# schematic.net
KiCad netlist of a schematic drawn in Altium Designer
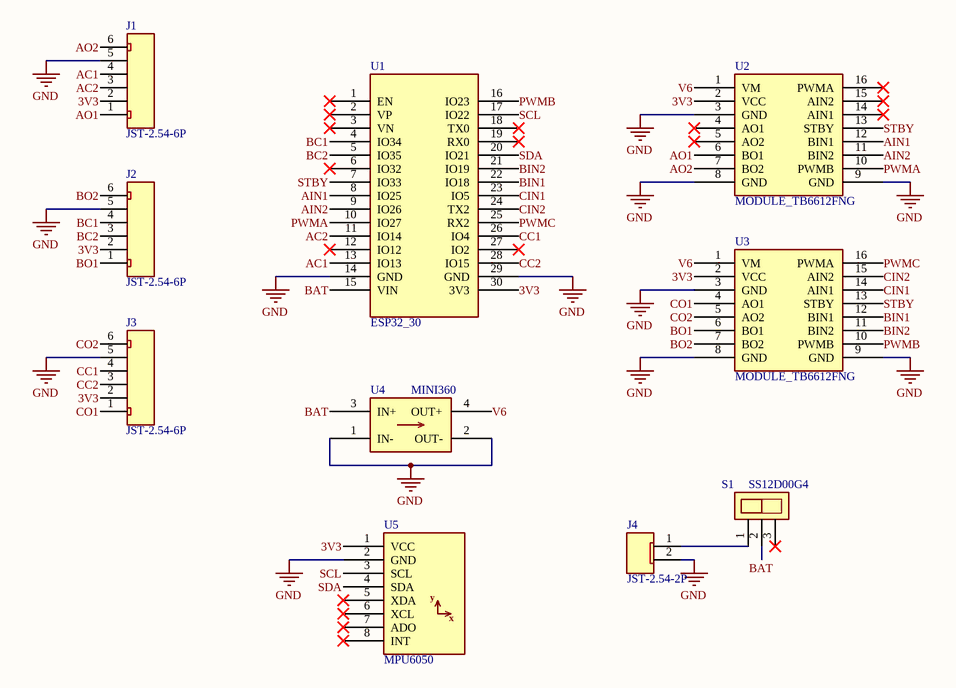
[diagram p0: schematic.SchDoc]

(export (version "E")
  (design (tool "Eeschema 10.0.6"))
  (components
    (comp (ref "J1")
      (value "JST-2.54-6P")
      (footprint "JST-2.54-6P")
      (description "Female Connector JST 6 Vias, 2.54mm.")
      (libsource (lib "Connectors") (part "JST-2.54-6P"))
    )
    (comp (ref "J2")
      (value "JST-2.54-6P")
      (footprint "JST-2.54-6P")
      (description "Female Connector JST 6 Vias, 2.54mm.")
      (libsource (lib "Connectors") (part "JST-2.54-6P"))
    )
    (comp (ref "J3")
      (value "JST-2.54-6P")
      (footprint "JST-2.54-6P")
      (description "Female Connector JST 6 Vias, 2.54mm.")
      (libsource (lib "Connectors") (part "JST-2.54-6P"))
    )
    (comp (ref "J4")
      (value "JST-2.54-2P")
      (footprint "JST-2.54-2P")
      (description "Female Connector JST 2 Vias, 2.54mm.")
      (libsource (lib "Connectors") (part "JST-2.54-2P"))
    )
    (comp (ref "S1")
      (value "SS12D00G4")
      (footprint "SS12D00G4")
      (description "Vertical Slide Switch 3 Pins.")
      (libsource (lib "Buttons & Switches") (part "SS12D00G4"))
    )
    (comp (ref "U1")
      (value "ESP32_30")
      (footprint "ESP32_30")
      (description "Microcontoller Board 30 Pins Wifi 2.4GHz BLE 4.2 ESP32-WROOM-32D")
      (libsource (lib "Espressif Microcontrollers") (part "ESP32_30"))
    )
    (comp (ref "U2")
      (value "MODULE_TB6612FNG")
      (footprint "MODULE_TB6612FNG")
      (description "Module Dual Motor Driver 2.5-13.5V 3.2A Peak 21x18mm")
      (libsource (lib "Motor Drivers") (part "MODULE_TB6612FNG"))
    )
    (comp (ref "U3")
      (value "MODULE_TB6612FNG")
      (footprint "MODULE_TB6612FNG")
      (description "Module Dual Motor Driver 2.5-13.5V 3.2A Peak 21x18mm")
      (libsource (lib "Motor Drivers") (part "MODULE_TB6612FNG"))
    )
    (comp (ref "U4")
      (value "MINI360")
      (footprint "MINI360")
      (description "MODULE BUCK STEP DOWN 3A 18x12mm")
      (libsource (lib "Voltage Regulators") (part "MINI360"))
    )
    (comp (ref "U5")
      (value "MPU6050")
      (footprint "MPU6050")
      (description "IMU ACCEL/GYRO 3-AXIS I2C")
      (libsource (lib "Sensors") (part "MPU6050"))
    )
  )
  (nets
    (net (code "1") (name "/3V3") (class "Default")
      (node (ref "J1") (pin "2") (pintype "passive"))
      (node (ref "J2") (pin "2") (pintype "passive"))
      (node (ref "J3") (pin "2") (pintype "passive"))
      (node (ref "U1") (pin "30") (pinfunction "3V3_30") (pintype "passive"))
      (node (ref "U2") (pin "2") (pinfunction "VCC_2") (pintype "passive"))
      (node (ref "U3") (pin "2") (pinfunction "VCC_2") (pintype "passive"))
      (node (ref "U5") (pin "1") (pinfunction "VCC_1") (pintype "passive"))
    )
    (net (code "2") (name "/AC1") (class "Default")
      (node (ref "J1") (pin "4") (pintype "passive"))
      (node (ref "U1") (pin "13") (pinfunction "IO13_13") (pintype "passive"))
    )
    (net (code "3") (name "/AC2") (class "Default")
      (node (ref "J1") (pin "3") (pintype "passive"))
      (node (ref "U1") (pin "11") (pinfunction "IO14_11") (pintype "passive"))
    )
    (net (code "4") (name "/AIN1") (class "Default")
      (node (ref "U1") (pin "8") (pinfunction "IO25_8") (pintype "passive"))
      (node (ref "U2") (pin "12") (pinfunction "BIN1_12") (pintype "passive"))
    )
    (net (code "5") (name "/AIN2") (class "Default")
      (node (ref "U1") (pin "9") (pinfunction "IO26_9") (pintype "passive"))
      (node (ref "U2") (pin "11") (pinfunction "BIN2_11") (pintype "passive"))
    )
    (net (code "6") (name "/AO1") (class "Default")
      (node (ref "J1") (pin "1") (pintype "passive"))
      (node (ref "U2") (pin "6") (pinfunction "BO1_6") (pintype "passive"))
    )
    (net (code "7") (name "/AO2") (class "Default")
      (node (ref "J1") (pin "6") (pintype "passive"))
      (node (ref "U2") (pin "7") (pinfunction "BO2_7") (pintype "passive"))
    )
    (net (code "8") (name "/BAT") (class "Default")
      (node (ref "S1") (pin "2") (pintype "passive"))
      (node (ref "U1") (pin "15") (pinfunction "VIN_15") (pintype "passive"))
      (node (ref "U4") (pin "3") (pinfunction "IN+_3") (pintype "passive"))
    )
    (net (code "9") (name "/BC1") (class "Default")
      (node (ref "J2") (pin "4") (pintype "passive"))
      (node (ref "U1") (pin "4") (pinfunction "IO34_4") (pintype "passive"))
    )
    (net (code "10") (name "/BC2") (class "Default")
      (node (ref "J2") (pin "3") (pintype "passive"))
      (node (ref "U1") (pin "5") (pinfunction "IO35_5") (pintype "passive"))
    )
    (net (code "11") (name "/BIN1") (class "Default")
      (node (ref "U1") (pin "22") (pinfunction "IO18_22") (pintype "passive"))
      (node (ref "U3") (pin "12") (pinfunction "BIN1_12") (pintype "passive"))
    )
    (net (code "12") (name "/BIN2") (class "Default")
      (node (ref "U1") (pin "21") (pinfunction "IO19_21") (pintype "passive"))
      (node (ref "U3") (pin "11") (pinfunction "BIN2_11") (pintype "passive"))
    )
    (net (code "13") (name "/BO1") (class "Default")
      (node (ref "J2") (pin "1") (pintype "passive"))
      (node (ref "U3") (pin "6") (pinfunction "BO1_6") (pintype "passive"))
    )
    (net (code "14") (name "/BO2") (class "Default")
      (node (ref "J2") (pin "6") (pintype "passive"))
      (node (ref "U3") (pin "7") (pinfunction "BO2_7") (pintype "passive"))
    )
    (net (code "15") (name "/CC1") (class "Default")
      (node (ref "J3") (pin "4") (pintype "passive"))
      (node (ref "U1") (pin "26") (pinfunction "IO4_26") (pintype "passive"))
    )
    (net (code "16") (name "/CC2") (class "Default")
      (node (ref "J3") (pin "3") (pintype "passive"))
      (node (ref "U1") (pin "28") (pinfunction "IO15_28") (pintype "passive"))
    )
    (net (code "17") (name "/CIN1") (class "Default")
      (node (ref "U1") (pin "23") (pinfunction "IO5_23") (pintype "passive"))
      (node (ref "U3") (pin "14") (pinfunction "AIN1_14") (pintype "passive"))
    )
    (net (code "18") (name "/CIN2") (class "Default")
      (node (ref "U1") (pin "24") (pinfunction "TX2_24") (pintype "passive"))
      (node (ref "U3") (pin "15") (pinfunction "AIN2_15") (pintype "passive"))
    )
    (net (code "19") (name "/CO1") (class "Default")
      (node (ref "J3") (pin "1") (pintype "passive"))
      (node (ref "U3") (pin "4") (pinfunction "AO1_4") (pintype "passive"))
    )
    (net (code "20") (name "/CO2") (class "Default")
      (node (ref "J3") (pin "6") (pintype "passive"))
      (node (ref "U3") (pin "5") (pinfunction "AO2_5") (pintype "passive"))
    )
    (net (code "21") (name "/PWMA") (class "Default")
      (node (ref "U1") (pin "10") (pinfunction "IO27_10") (pintype "passive"))
      (node (ref "U2") (pin "10") (pinfunction "PWMB_10") (pintype "passive"))
    )
    (net (code "22") (name "/PWMB") (class "Default")
      (node (ref "U1") (pin "16") (pinfunction "IO23_16") (pintype "passive"))
      (node (ref "U3") (pin "10") (pinfunction "PWMB_10") (pintype "passive"))
    )
    (net (code "23") (name "/PWMC") (class "Default")
      (node (ref "U1") (pin "25") (pinfunction "RX2_25") (pintype "passive"))
      (node (ref "U3") (pin "16") (pinfunction "PWMA_16") (pintype "passive"))
    )
    (net (code "24") (name "/SCL") (class "Default")
      (node (ref "U1") (pin "17") (pinfunction "IO22_17") (pintype "passive"))
      (node (ref "U5") (pin "3") (pinfunction "SCL_3") (pintype "passive"))
    )
    (net (code "25") (name "/SDA") (class "Default")
      (node (ref "U1") (pin "20") (pinfunction "IO21_20") (pintype "passive"))
      (node (ref "U5") (pin "4") (pinfunction "SDA_4") (pintype "passive"))
    )
    (net (code "26") (name "/STBY") (class "Default")
      (node (ref "U1") (pin "7") (pinfunction "IO33_7") (pintype "passive"))
      (node (ref "U2") (pin "13") (pinfunction "STBY_13") (pintype "passive"))
      (node (ref "U3") (pin "13") (pinfunction "STBY_13") (pintype "passive"))
    )
    (net (code "27") (name "/V6") (class "Default")
      (node (ref "U2") (pin "1") (pinfunction "VM_1") (pintype "passive"))
      (node (ref "U3") (pin "1") (pinfunction "VM_1") (pintype "passive"))
      (node (ref "U4") (pin "4") (pinfunction "OUT+_4") (pintype "passive"))
    )
    (net (code "28") (name "GND") (class "Default")
      (node (ref "J1") (pin "5") (pintype "passive"))
      (node (ref "J2") (pin "5") (pintype "passive"))
      (node (ref "J3") (pin "5") (pintype "passive"))
      (node (ref "J4") (pin "2") (pintype "passive"))
      (node (ref "U1") (pin "14") (pinfunction "GND_14") (pintype "passive"))
      (node (ref "U1") (pin "29") (pinfunction "GND_29") (pintype "passive"))
      (node (ref "U2") (pin "3") (pinfunction "GND_3") (pintype "passive"))
      (node (ref "U2") (pin "8") (pinfunction "GND_8") (pintype "passive"))
      (node (ref "U2") (pin "9") (pinfunction "GND_9") (pintype "passive"))
      (node (ref "U3") (pin "3") (pinfunction "GND_3") (pintype "passive"))
      (node (ref "U3") (pin "8") (pinfunction "GND_8") (pintype "passive"))
      (node (ref "U3") (pin "9") (pinfunction "GND_9") (pintype "passive"))
      (node (ref "U4") (pin "1") (pinfunction "IN-_1") (pintype "passive"))
      (node (ref "U4") (pin "2") (pinfunction "OUT-_2") (pintype "passive"))
      (node (ref "U5") (pin "2") (pinfunction "GND_2") (pintype "passive"))
    )
    (net (code "29") (name "Net-(J4-Pad1)") (class "Default")
      (node (ref "J4") (pin "1") (pintype "passive"))
      (node (ref "S1") (pin "1") (pintype "passive"))
    )
    (net (code "30") (name "unconnected-(S1-Pad3)") (class "Default")
      (node (ref "S1") (pin "3") (pintype "passive+no_connect"))
    )
    (net (code "31") (name "unconnected-(U1-EN-Pad1)") (class "Default")
      (node (ref "U1") (pin "1") (pinfunction "EN_1") (pintype "passive+no_connect"))
    )
    (net (code "32") (name "unconnected-(U1-IO2-Pad27)") (class "Default")
      (node (ref "U1") (pin "27") (pinfunction "IO2_27") (pintype "passive+no_connect"))
    )
    (net (code "33") (name "unconnected-(U1-IO12-Pad12)") (class "Default")
      (node (ref "U1") (pin "12") (pinfunction "IO12_12") (pintype "passive+no_connect"))
    )
    (net (code "34") (name "unconnected-(U1-IO32-Pad6)") (class "Default")
      (node (ref "U1") (pin "6") (pinfunction "IO32_6") (pintype "passive+no_connect"))
    )
    (net (code "35") (name "unconnected-(U1-RX0-Pad19)") (class "Default")
      (node (ref "U1") (pin "19") (pinfunction "RX0_19") (pintype "passive+no_connect"))
    )
    (net (code "36") (name "unconnected-(U1-TX0-Pad18)") (class "Default")
      (node (ref "U1") (pin "18") (pinfunction "TX0_18") (pintype "passive+no_connect"))
    )
    (net (code "37") (name "unconnected-(U1-VN-Pad3)") (class "Default")
      (node (ref "U1") (pin "3") (pinfunction "VN_3") (pintype "passive+no_connect"))
    )
    (net (code "38") (name "unconnected-(U1-VP-Pad2)") (class "Default")
      (node (ref "U1") (pin "2") (pinfunction "VP_2") (pintype "passive+no_connect"))
    )
    (net (code "39") (name "unconnected-(U2-AIN1-Pad14)") (class "Default")
      (node (ref "U2") (pin "14") (pinfunction "AIN1_14") (pintype "passive+no_connect"))
    )
    (net (code "40") (name "unconnected-(U2-AIN2-Pad15)") (class "Default")
      (node (ref "U2") (pin "15") (pinfunction "AIN2_15") (pintype "passive+no_connect"))
    )
    (net (code "41") (name "unconnected-(U2-AO1-Pad4)") (class "Default")
      (node (ref "U2") (pin "4") (pinfunction "AO1_4") (pintype "passive+no_connect"))
    )
    (net (code "42") (name "unconnected-(U2-AO2-Pad5)") (class "Default")
      (node (ref "U2") (pin "5") (pinfunction "AO2_5") (pintype "passive+no_connect"))
    )
    (net (code "43") (name "unconnected-(U2-PWMA-Pad16)") (class "Default")
      (node (ref "U2") (pin "16") (pinfunction "PWMA_16") (pintype "passive+no_connect"))
    )
    (net (code "44") (name "unconnected-(U5-ADO-Pad7)") (class "Default")
      (node (ref "U5") (pin "7") (pinfunction "ADO_7") (pintype "passive+no_connect"))
    )
    (net (code "45") (name "unconnected-(U5-INT-Pad8)") (class "Default")
      (node (ref "U5") (pin "8") (pinfunction "INT_8") (pintype "passive+no_connect"))
    )
    (net (code "46") (name "unconnected-(U5-XCL-Pad6)") (class "Default")
      (node (ref "U5") (pin "6") (pinfunction "XCL_6") (pintype "passive+no_connect"))
    )
    (net (code "47") (name "unconnected-(U5-XDA-Pad5)") (class "Default")
      (node (ref "U5") (pin "5") (pinfunction "XDA_5") (pintype "passive+no_connect"))
    )
  )
)
